# LCD-Panel.net
KiCad netlist of a schematic drawn in EAGLE
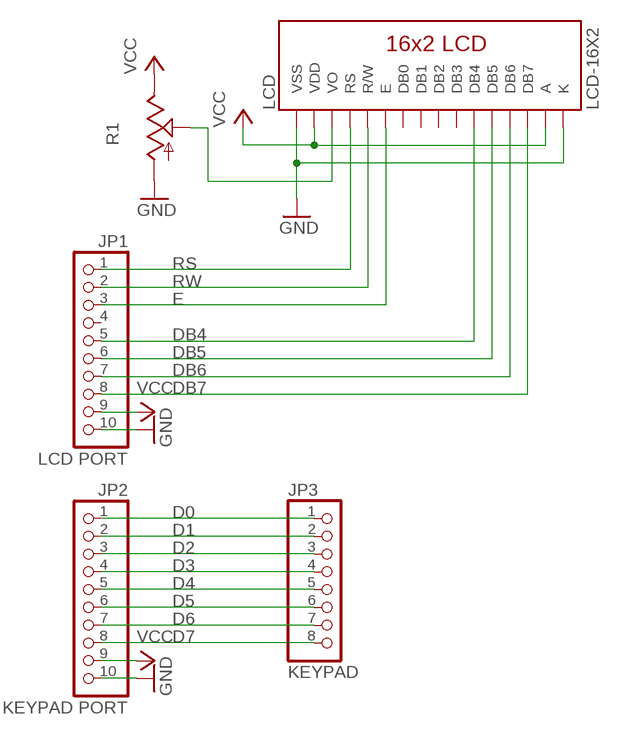
[diagram p0: schematic, sheet 1]

(export (version "E")
  (design (tool "Eeschema 10.0.6"))
  (components
    (comp (ref "JP1")
      (value "LCD PORT")
      (footprint "eagle-import:1X10")
      (libsource (lib "eagle-import") (part "PINHD-1X10"))
    )
    (comp (ref "JP2")
      (value "KEYPAD PORT")
      (footprint "eagle-import:1X10")
      (libsource (lib "eagle-import") (part "PINHD-1X10"))
    )
    (comp (ref "JP3")
      (value "KEYPAD")
      (footprint "eagle-import:1X08")
      (libsource (lib "eagle-import") (part "PINHD-1X8"))
    )
    (comp (ref "LCD")
      (value "LCD-16X2")
      (footprint "eagle-import:LCD-16X2")
      (libsource (lib "eagle-import") (part "LCD-16X2"))
    )
    (comp (ref "R1")
      (value "TRIMPOTCA6V")
      (footprint "eagle-import:CA6V")
      (libsource (lib "eagle-import") (part "TRIMPOTCA6V"))
    )
  )
  (nets
    (net (code "1") (name "/D0") (class "Default")
      (node (ref "JP2") (pin "1") (pinfunction "1_1") (pintype "passive"))
      (node (ref "JP3") (pin "1") (pinfunction "1_1") (pintype "passive"))
    )
    (net (code "2") (name "/D1") (class "Default")
      (node (ref "JP2") (pin "2") (pinfunction "2_2") (pintype "passive"))
      (node (ref "JP3") (pin "2") (pinfunction "2_2") (pintype "passive"))
    )
    (net (code "3") (name "/D2") (class "Default")
      (node (ref "JP2") (pin "3") (pinfunction "3_3") (pintype "passive"))
      (node (ref "JP3") (pin "3") (pinfunction "3_3") (pintype "passive"))
    )
    (net (code "4") (name "/D3") (class "Default")
      (node (ref "JP2") (pin "4") (pinfunction "4_4") (pintype "passive"))
      (node (ref "JP3") (pin "4") (pinfunction "4_4") (pintype "passive"))
    )
    (net (code "5") (name "/D4") (class "Default")
      (node (ref "JP2") (pin "5") (pinfunction "5_5") (pintype "passive"))
      (node (ref "JP3") (pin "5") (pinfunction "5_5") (pintype "passive"))
    )
    (net (code "6") (name "/D5") (class "Default")
      (node (ref "JP2") (pin "6") (pinfunction "6_6") (pintype "passive"))
      (node (ref "JP3") (pin "6") (pinfunction "6_6") (pintype "passive"))
    )
    (net (code "7") (name "/D6") (class "Default")
      (node (ref "JP2") (pin "7") (pinfunction "7_7") (pintype "passive"))
      (node (ref "JP3") (pin "7") (pinfunction "7_7") (pintype "passive"))
    )
    (net (code "8") (name "/D7") (class "Default")
      (node (ref "JP2") (pin "8") (pinfunction "8_8") (pintype "passive"))
      (node (ref "JP3") (pin "8") (pinfunction "8_8") (pintype "passive"))
    )
    (net (code "9") (name "/DB4") (class "Default")
      (node (ref "JP1") (pin "5") (pinfunction "5_5") (pintype "passive"))
      (node (ref "LCD") (pin "11") (pinfunction "DB4_11") (pintype "bidirectional"))
    )
    (net (code "10") (name "/DB5") (class "Default")
      (node (ref "JP1") (pin "6") (pinfunction "6_6") (pintype "passive"))
      (node (ref "LCD") (pin "12") (pinfunction "DB5_12") (pintype "bidirectional"))
    )
    (net (code "11") (name "/DB6") (class "Default")
      (node (ref "JP1") (pin "7") (pinfunction "7_7") (pintype "passive"))
      (node (ref "LCD") (pin "13") (pinfunction "DB6_13") (pintype "bidirectional"))
    )
    (net (code "12") (name "/DB7") (class "Default")
      (node (ref "JP1") (pin "8") (pinfunction "8_8") (pintype "passive"))
      (node (ref "LCD") (pin "14") (pinfunction "DB7_14") (pintype "bidirectional"))
    )
    (net (code "13") (name "/E") (class "Default")
      (node (ref "JP1") (pin "3") (pinfunction "3_3") (pintype "passive"))
      (node (ref "LCD") (pin "6") (pinfunction "E_6") (pintype "input"))
    )
    (net (code "14") (name "/RS") (class "Default")
      (node (ref "JP1") (pin "1") (pinfunction "1_1") (pintype "passive"))
      (node (ref "LCD") (pin "4") (pinfunction "RS_4") (pintype "input"))
    )
    (net (code "15") (name "/RW") (class "Default")
      (node (ref "JP1") (pin "2") (pinfunction "2_2") (pintype "passive"))
      (node (ref "LCD") (pin "5") (pinfunction "R/W_5") (pintype "input"))
    )
    (net (code "16") (name "GND") (class "Default")
      (node (ref "JP1") (pin "10") (pinfunction "10_10") (pintype "passive"))
      (node (ref "JP2") (pin "10") (pinfunction "10_10") (pintype "passive"))
      (node (ref "LCD") (pin "1") (pinfunction "VSS_1") (pintype "power_in"))
      (node (ref "LCD") (pin "16") (pinfunction "K_16") (pintype "power_in"))
      (node (ref "R1") (pin "A") (pinfunction "A_A") (pintype "passive"))
    )
    (net (code "17") (name "Net-(LCD-VO)") (class "Default")
      (node (ref "LCD") (pin "3") (pinfunction "VO_3") (pintype "bidirectional"))
      (node (ref "R1") (pin "S") (pinfunction "S_S") (pintype "passive"))
    )
    (net (code "18") (name "VCC") (class "Default")
      (node (ref "JP1") (pin "9") (pinfunction "9_9") (pintype "passive"))
      (node (ref "JP2") (pin "9") (pinfunction "9_9") (pintype "passive"))
      (node (ref "LCD") (pin "15") (pinfunction "A_15") (pintype "power_in"))
      (node (ref "LCD") (pin "2") (pinfunction "VDD_2") (pintype "power_in"))
      (node (ref "R1") (pin "E") (pinfunction "E_E") (pintype "passive"))
    )
    (net (code "19") (name "unconnected-(JP1-Pad4)") (class "Default")
      (node (ref "JP1") (pin "4") (pinfunction "4_4") (pintype "passive"))
    )
    (net (code "20") (name "unconnected-(LCD-DB0-Pad7)") (class "Default")
      (node (ref "LCD") (pin "7") (pinfunction "DB0_7") (pintype "bidirectional"))
    )
    (net (code "21") (name "unconnected-(LCD-DB1-Pad8)") (class "Default")
      (node (ref "LCD") (pin "8") (pinfunction "DB1_8") (pintype "bidirectional"))
    )
    (net (code "22") (name "unconnected-(LCD-DB2-Pad9)") (class "Default")
      (node (ref "LCD") (pin "9") (pinfunction "DB2_9") (pintype "bidirectional"))
    )
    (net (code "23") (name "unconnected-(LCD-DB3-Pad10)") (class "Default")
      (node (ref "LCD") (pin "10") (pinfunction "DB3_10") (pintype "bidirectional"))
    )
  )
)
